# ImpactNode.net
KiCad netlist of a schematic drawn in Altium Designer
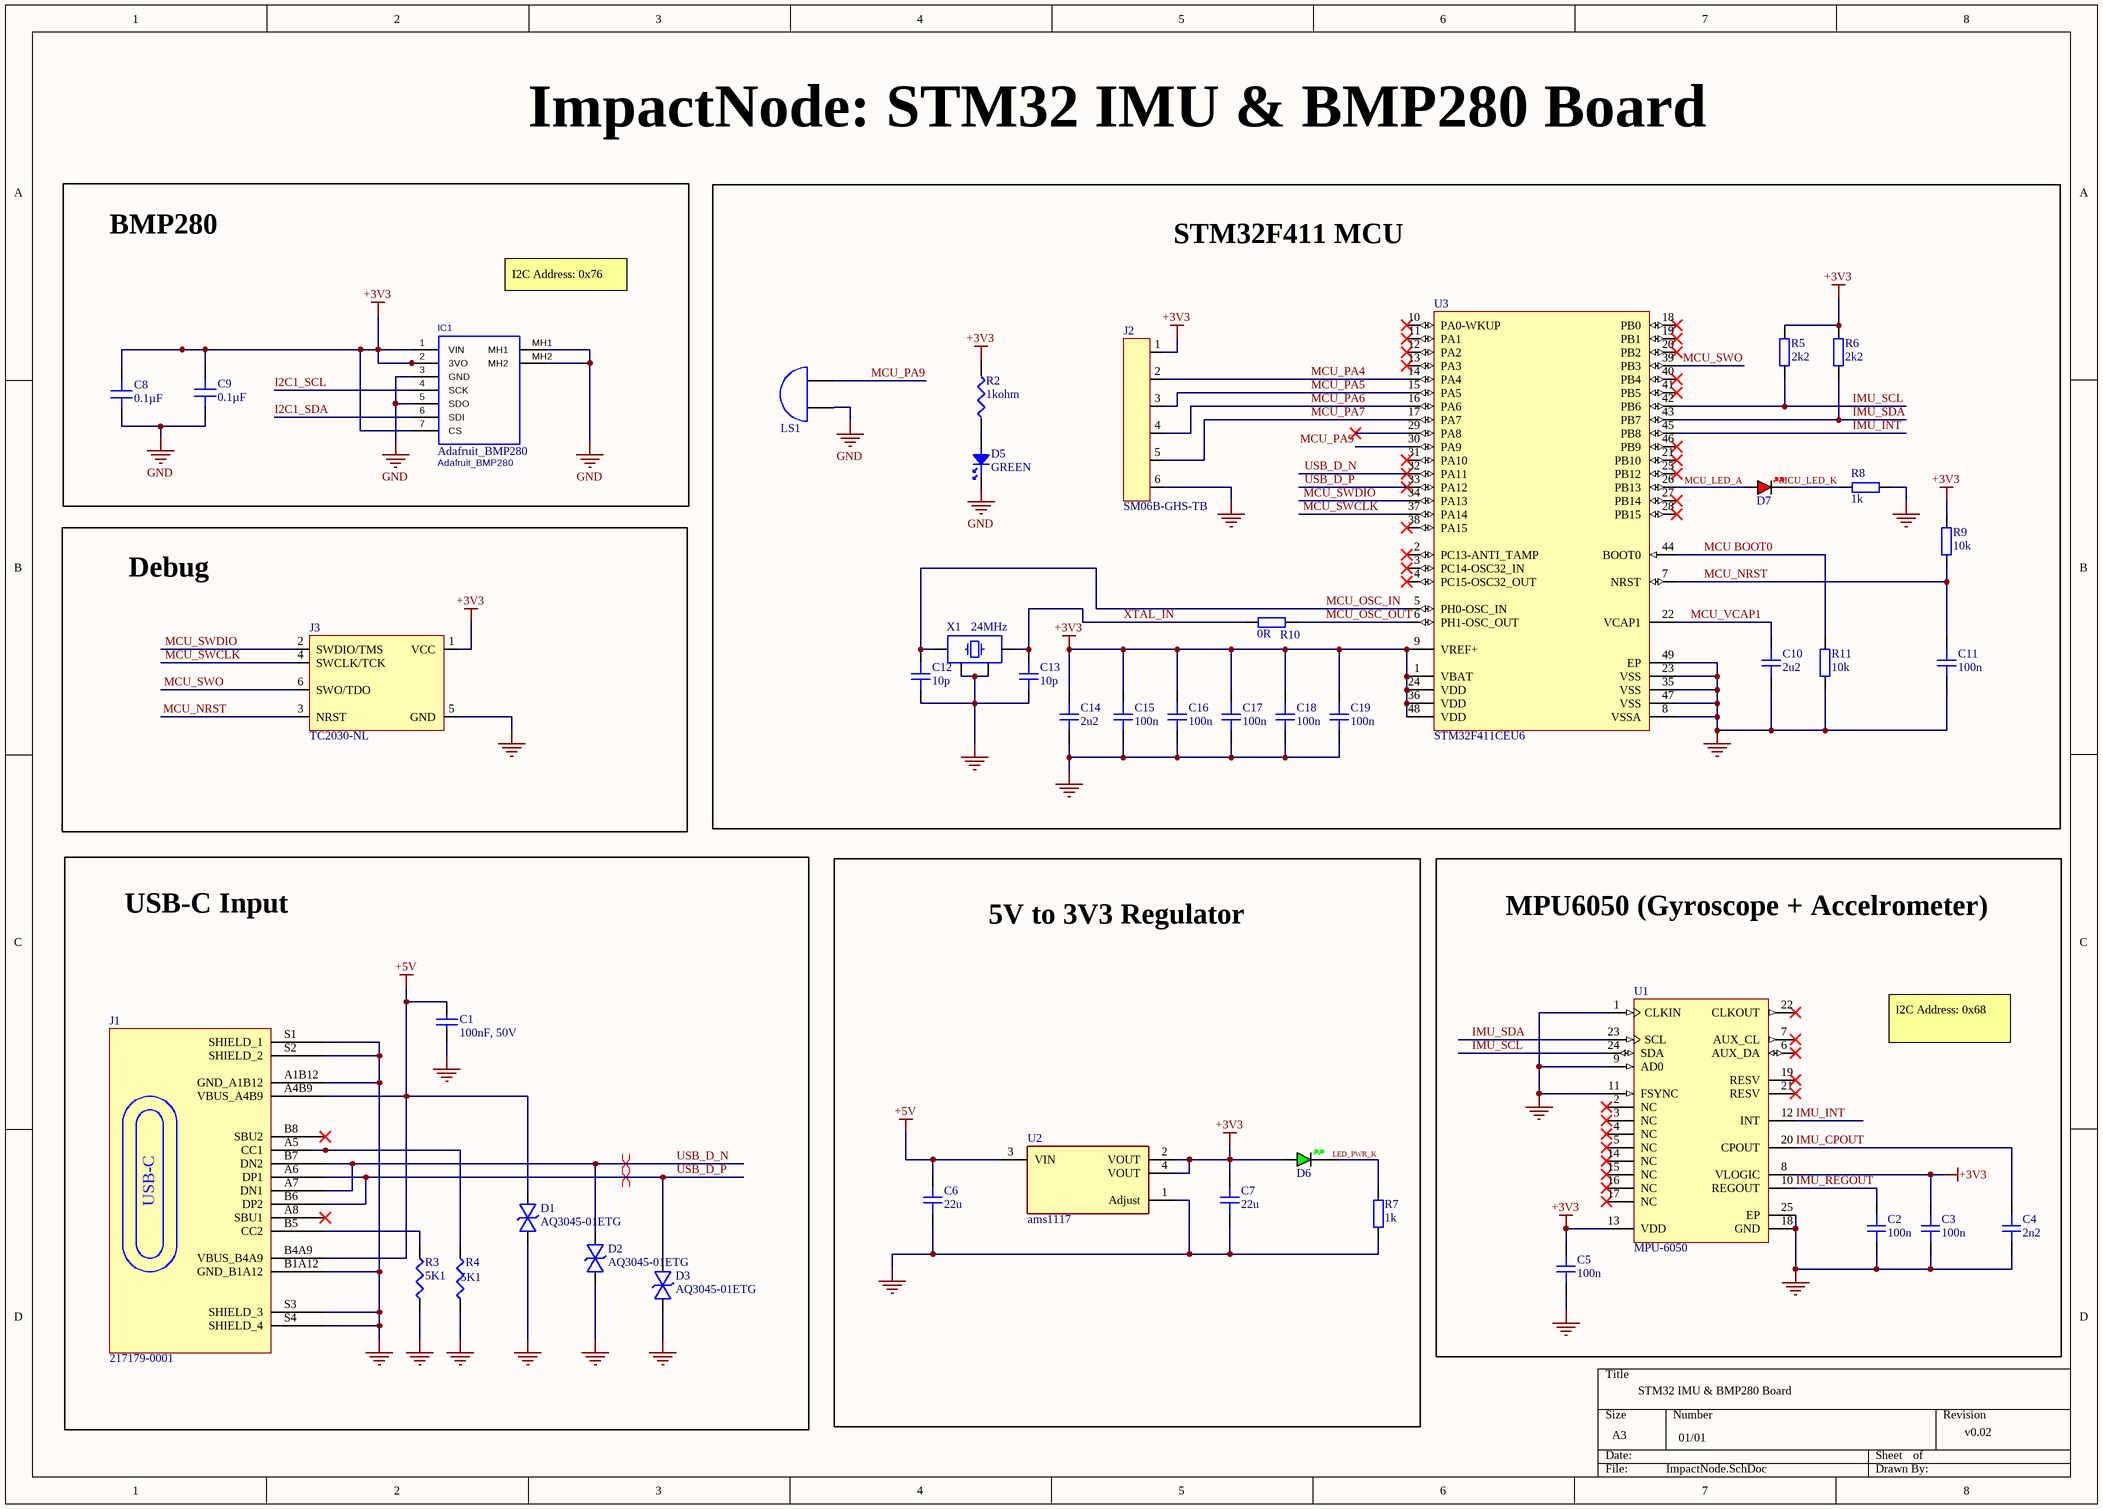
[diagram p0: ImpactNode.SchDoc]

(export (version "E")
  (design (tool "Eeschema 10.0.6"))
  (components
    (comp (ref "C1")
      (value "100nF, 50V")
      (footprint "CAPC1005X55N")
      (description "CAP CER 0.1UF 50V X7R 0402")
      (fields
        (field (name "MANUFACTURER") "Samsung Electro-Mechanics")
        (field (name "MANUFACTURER PART NUMBER") "CL05B104KB5NNNC")
      )
      (libsource (lib "SchLIb") (part "CL05B104KB5NNNC"))
    )
    (comp (ref "C2")
      (value "100n")
      (footprint "CAP_0402")
      (description "Capacitor SMD 0402 16V")
      (libsource (lib "Schematic-Lib-PhilsLab") (part "CAP_0402"))
    )
    (comp (ref "C3")
      (value "100n")
      (footprint "CAP_0402")
      (description "Capacitor SMD 0402 16V")
      (libsource (lib "Schematic-Lib-PhilsLab") (part "CAP_0402"))
    )
    (comp (ref "C4")
      (value "2n2")
      (footprint "CAP_0402")
      (description "Capacitor SMD 0402 16V")
      (libsource (lib "Schematic-Lib-PhilsLab") (part "CAP_0402"))
    )
    (comp (ref "C5")
      (value "100n")
      (footprint "CAP_0402")
      (description "Capacitor SMD 0402")
      (libsource (lib "Schematic-Lib-PhilsLab") (part "CAP_0402"))
    )
    (comp (ref "C6")
      (value "22u")
      (footprint "CAP_0805")
      (description "Capacitor SMD 0805 16V")
      (libsource (lib "Schematic-Lib-PhilsLab") (part "CAP_0805"))
    )
    (comp (ref "C7")
      (value "22u")
      (footprint "CAP_0805")
      (description "Capacitor SMD 0805 16V")
      (libsource (lib "Schematic-Lib-PhilsLab") (part "CAP_0805"))
    )
    (comp (ref "C8")
      (value "0.1µF")
      (footprint "CAP 0603_1608")
      (description "CAP CER 0.1UF 10V X7R 0603")
      (fields
        (field (name "PART NUMBER") "LD03ZC104KAB2A")
        (field (name "CAPACITANCE") "0.1µF")
        (field (name "MANUFACTURER") "AVX Corporation")
      )
      (libsource (lib "Celestial Altium Library - altium_library") (part "Capacitor"))
    )
    (comp (ref "C9")
      (value "0.1µF")
      (footprint "CAP 0603_1608")
      (description "CAP CER 0.1UF 10V X7R 0603")
      (fields
        (field (name "PART NUMBER") "LD03ZC104KAB2A")
        (field (name "CAPACITANCE") "0.1µF")
        (field (name "MANUFACTURER") "AVX Corporation")
      )
      (libsource (lib "Celestial Altium Library - altium_library") (part "Capacitor"))
    )
    (comp (ref "C10")
      (value "2u2")
      (footprint "CAP_0603")
      (description "Capacitor SMD 0603")
      (libsource (lib "Schematic-Lib-PhilsLab") (part "CAP_0603"))
    )
    (comp (ref "C11")
      (value "100n")
      (footprint "CAP_0402")
      (description "Capacitor SMD 0402")
      (libsource (lib "Schematic-Lib-PhilsLab") (part "CAP_0402"))
    )
    (comp (ref "C12")
      (value "10p")
      (footprint "CAP_0402")
      (description "Capacitor SMD 0402 16V")
      (libsource (lib "Schematic-Lib-PhilsLab") (part "CAP_0402"))
    )
    (comp (ref "C13")
      (value "10p")
      (footprint "CAP_0402")
      (description "Capacitor SMD 0402 16V")
      (libsource (lib "Schematic-Lib-PhilsLab") (part "CAP_0402"))
    )
    (comp (ref "C14")
      (value "2u2")
      (footprint "CAP_0603")
      (description "Capacitor SMD 0603")
      (libsource (lib "Schematic-Lib-PhilsLab") (part "CAP_0603"))
    )
    (comp (ref "C15")
      (value "100n")
      (footprint "CAP_0402")
      (description "Capacitor SMD 0402")
      (libsource (lib "Schematic-Lib-PhilsLab") (part "CAP_0402"))
    )
    (comp (ref "C16")
      (value "100n")
      (footprint "CAP_0402")
      (description "Capacitor SMD 0402")
      (libsource (lib "Schematic-Lib-PhilsLab") (part "CAP_0402"))
    )
    (comp (ref "C17")
      (value "100n")
      (footprint "CAP_0402")
      (description "Capacitor SMD 0402")
      (libsource (lib "Schematic-Lib-PhilsLab") (part "CAP_0402"))
    )
    (comp (ref "C18")
      (value "100n")
      (footprint "CAP_0402")
      (description "Capacitor SMD 0402")
      (libsource (lib "Schematic-Lib-PhilsLab") (part "CAP_0402"))
    )
    (comp (ref "C19")
      (value "100n")
      (footprint "CAP_0402")
      (description "Capacitor SMD 0402")
      (libsource (lib "Schematic-Lib-PhilsLab") (part "CAP_0402"))
    )
    (comp (ref "D1")
      (value "AQ3045-01ETG")
      (footprint "SOD882")
      (description "Bi 30Kv 5V 0.35Pf Automotve Tvs Sod882/ T&r Rohs Compliant: Yes ¦Littelfuse AQ3045-01ETG")
      (fields (field (name "MANUFACTURER") "Littelfuse"))
      (libsource (lib "SchLIb") (part "AQ3045-01ETG"))
    )
    (comp (ref "D2")
      (value "AQ3045-01ETG")
      (footprint "SOD882")
      (description "Bi 30Kv 5V 0.35Pf Automotve Tvs Sod882/ T&r Rohs Compliant: Yes ¦Littelfuse AQ3045-01ETG")
      (fields (field (name "MANUFACTURER") "Littelfuse"))
      (libsource (lib "SchLIb") (part "AQ3045-01ETG"))
    )
    (comp (ref "D3")
      (value "AQ3045-01ETG")
      (footprint "SOD882")
      (description "Bi 30Kv 5V 0.35Pf Automotve Tvs Sod882/ T&r Rohs Compliant: Yes ¦Littelfuse AQ3045-01ETG")
      (fields (field (name "MANUFACTURER") "Littelfuse"))
      (libsource (lib "SchLIb") (part "AQ3045-01ETG"))
    )
    (comp (ref "D5")
      (value "GREEN")
      (footprint "LED_0603")
      (description "Single Color LED, Yellow Green, 0.5mm")
      (fields
        (field (name "MANUFACTURER") "Vishay")
        (field (name "MANUFACTURER PART NUMBER") "VLMG1500-GS08")
      )
      (libsource (lib "Schlib") (part "VLMG1500-GS08"))
    )
    (comp (ref "D6")
      (value "GREEN")
      (footprint "LED_0402_GREEN")
      (description "LED 0402 GREEN SMD")
      (libsource (lib "Schematic-Lib-PhilsLab") (part "LED_0402_GREEN"))
    )
    (comp (ref "D7")
      (value "RED")
      (footprint "LED_0402_RED")
      (description "LED 0402 RED SMD")
      (libsource (lib "Schematic-Lib-PhilsLab") (part "LED_0402_RED"))
    )
    (comp (ref "IC1")
      (value "Adafruit_BMP280")
      (footprint "AdafruitBMP280")
      (description "Adafruit BMP280 Barometric Pressure + Temperature Sensor Breakout")
      (fields
        (field (name "MANUFACTURER_PART_NUMBER") "Adafruit BMP280")
        (field (name "ALTIUM_VALUE") "Adafruit_BMP280")
      )
      (libsource (lib "Adafruit_BMP280") (part "Adafruit_BMP280"))
    )
    (comp (ref "J1")
      (value "217179-0001")
      (footprint "FP-2171790001-MFG")
      (description "USB Connector, USB Type C, USB 2.0, Receptacle, 16 Ways, Surface Mount, Through Hole Mount")
      (fields (field (name "MANUFACTURER") "Molex") (field (name "LCSC PART NUMBER") "C3197684"))
      (libsource (lib "SchLIb") (part "217179-0001"))
    )
    (comp (ref "J2")
      (value "SM06B-GHS-TB")
      (footprint "HDR1X6")
      (description "Header Connector 6 Position 1.25MM Pitch SMD Horizontal JST GH")
      (fields (field (name "MANUFACTURER") "JST"))
      (libsource (lib "Schematic-Lib-PhilsLab") (part "SM06B-GHS-TB"))
    )
    (comp (ref "J3")
      (value "TC2030-NL")
      (footprint "TC2030-NL-FP")
      (description "Tag-Connect No-Solder SWD Debug Connector (No Legs) DO NOT PLACE")
      (fields
        (field (name "MANUFACTURER") "Tag-Connect")
        (field (name "MANUFACTURER PART NUMBER") "TC2030-NL-FP")
      )
      (libsource (lib "Schematic-Lib-PhilsLab") (part "TC2030-NL"))
    )
    (comp (ref "LS1")
      (value "buzzer")
      (footprint "PIN2")
      (description "Buzzer")
      (fields (field (name "PUBLISHER") "Altium Limited"))
      (libsource (lib "Miscellaneous Devices") (part "Bell"))
    )
    (comp (ref "R2")
      (value "1kohm")
      (footprint "R0402")
      (description "RES 1K OHM 1% 1/16W 0402")
      (fields
        (field (name "MANUFACTURER") "Yageo")
        (field (name "MANUFACTURER PART NUMBER") "RC0402FR-071KL")
      )
      (libsource (lib "Schlib") (part "RC0402FR-071KL"))
    )
    (comp (ref "R3")
      (value "5K1")
      (footprint "RESC1005X37N")
      (description "Res Thick Film 0402 5.1K Ohm 1% 0.063W(1/16W) ±100ppm/C Pad SMD Automotive T/R")
      (fields
        (field (name "MANUFACTURER") "Yageo Group")
        (field (name "MANUFACTURER PART NUMBER") "AC0402FR-075K1L")
      )
      (libsource (lib "SchLIb") (part "AC0402FR-075K1L"))
    )
    (comp (ref "R4")
      (value "5K1")
      (footprint "RESC1005X37N")
      (description "Res Thick Film 0402 5.1K Ohm 1% 0.063W(1/16W) ±100ppm/C Pad SMD Automotive T/R")
      (fields
        (field (name "MANUFACTURER") "Yageo Group")
        (field (name "MANUFACTURER PART NUMBER") "AC0402FR-075K1L")
      )
      (libsource (lib "SchLIb") (part "AC0402FR-075K1L"))
    )
    (comp (ref "R5")
      (value "2k2")
      (footprint "RES_0402")
      (description "Resistor SMD 0402")
      (libsource (lib "Schematic-Lib-PhilsLab") (part "RES_0402"))
    )
    (comp (ref "R6")
      (value "2k2")
      (footprint "RES_0402")
      (description "Resistor SMD 0402")
      (libsource (lib "Schematic-Lib-PhilsLab") (part "RES_0402"))
    )
    (comp (ref "R7")
      (value "1k")
      (footprint "RES_0402")
      (description "Resistor SMD 0402")
      (libsource (lib "Schematic-Lib-PhilsLab") (part "RES_0402"))
    )
    (comp (ref "R8")
      (value "1k")
      (footprint "RES_0402")
      (description "Resistor SMD 0402")
      (libsource (lib "Schematic-Lib-PhilsLab") (part "RES_0402"))
    )
    (comp (ref "R9")
      (value "10k")
      (footprint "RES_0402")
      (description "Resistor SMD 0402")
      (libsource (lib "Schematic-Lib-PhilsLab") (part "RES_0402"))
    )
    (comp (ref "R10")
      (value "0R")
      (footprint "RES_0402")
      (description "Resistor SMD 0402 0R")
      (libsource (lib "Schematic-Lib-PhilsLab") (part "RES_0402"))
    )
    (comp (ref "R11")
      (value "10k")
      (footprint "RES_0402")
      (description "Resistor SMD 0402")
      (libsource (lib "Schematic-Lib-PhilsLab") (part "RES_0402"))
    )
    (comp (ref "U1")
      (value "MPU-6050")
      (footprint "IS-QFN-24_V")
      (fields (field (name "MANUFACTURER") "InvenSense"))
      (libsource (lib "Altium Content Vault") (part "IS-MPU-6050-QFN-24"))
    )
    (comp (ref "U2")
      (value "ams1117")
      (footprint "FP-ams1117-IPC_C")
      (description "1A LOW DROPOUT VOLTAGE REGULATOR")
      (libsource (lib "Altium Content Vault") (part "59ad430b93a2c51b3e6ee7c3b069677"))
    )
    (comp (ref "U3")
      (value "STM32F411CEU6")
      (footprint "STM-UFQFPN48_L")
      (libsource (lib "Altium Content Vault") (part "MC-ARM-STM32F411-UFQFPN48"))
    )
    (comp (ref "X1")
      (value "24MHz")
      (footprint "XTAL_3225")
      (description "Crystal SMD 24MHz 10PPM 7pF 3225")
      (fields
        (field (name "MANUFACTURER") "Epson")
        (field (name "MANUFACTURER PART NUMBER") "TSX-3225 24.0000MF15X-AC")
      )
      (libsource (lib "Schematic-Lib-PhilsLab") (part "TSX-3225_24.0000MF15X-AC"))
    )
  )
  (nets
    (net (code "1") (name "+3V3") (class "Default")
      (node (ref "C14") (pin "2") (pinfunction "2_2") (pintype "passive"))
      (node (ref "C15") (pin "2") (pinfunction "2_2") (pintype "passive"))
      (node (ref "C16") (pin "2") (pinfunction "2_2") (pintype "passive"))
      (node (ref "C17") (pin "2") (pinfunction "2_2") (pintype "passive"))
      (node (ref "C18") (pin "2") (pinfunction "2_2") (pintype "passive"))
      (node (ref "C19") (pin "2") (pinfunction "2_2") (pintype "passive"))
      (node (ref "C3") (pin "2") (pinfunction "2_2") (pintype "passive"))
      (node (ref "C5") (pin "2") (pinfunction "2_2") (pintype "passive"))
      (node (ref "C7") (pin "2") (pinfunction "2_2") (pintype "passive"))
      (node (ref "C8") (pin "2") (pinfunction "2_2") (pintype "passive"))
      (node (ref "C9") (pin "2") (pinfunction "2_2") (pintype "passive"))
      (node (ref "D6") (pin "A") (pinfunction "A_A") (pintype "passive"))
      (node (ref "IC1") (pin "1") (pinfunction "VIN_1") (pintype "passive"))
      (node (ref "IC1") (pin "2") (pinfunction "3VO_2") (pintype "passive"))
      (node (ref "IC1") (pin "7") (pinfunction "CS_7") (pintype "passive"))
      (node (ref "J2") (pin "1") (pinfunction "1_1") (pintype "passive"))
      (node (ref "J3") (pin "1") (pinfunction "VCC_1") (pintype "passive"))
      (node (ref "R2") (pin "2") (pinfunction "2_2") (pintype "passive"))
      (node (ref "R5") (pin "2") (pinfunction "2_2") (pintype "passive"))
      (node (ref "R6") (pin "2") (pinfunction "2_2") (pintype "passive"))
      (node (ref "R9") (pin "2") (pinfunction "2_2") (pintype "passive"))
      (node (ref "U1") (pin "13") (pinfunction "VDD_13") (pintype "power_in"))
      (node (ref "U1") (pin "8") (pinfunction "VLOGIC_8") (pintype "power_in"))
      (node (ref "U2") (pin "2") (pinfunction "VOUT_2") (pintype "passive"))
      (node (ref "U2") (pin "4") (pinfunction "VOUT_4") (pintype "passive"))
      (node (ref "U3") (pin "1") (pinfunction "VBAT_1") (pintype "power_in"))
      (node (ref "U3") (pin "24") (pinfunction "VDD_24") (pintype "power_in"))
      (node (ref "U3") (pin "36") (pinfunction "VDD_36") (pintype "power_in"))
      (node (ref "U3") (pin "48") (pinfunction "VDD_48") (pintype "power_in"))
      (node (ref "U3") (pin "9") (pinfunction "VREF+_9") (pintype "power_in"))
    )
    (net (code "2") (name "+5V") (class "Default")
      (node (ref "C1") (pin "2") (pinfunction "2_2") (pintype "passive"))
      (node (ref "C6") (pin "2") (pinfunction "2_2") (pintype "passive"))
      (node (ref "D1") (pin "2") (pinfunction "2_2") (pintype "passive"))
      (node (ref "J1") (pin "A4B9") (pinfunction "VBUS_A4B9_A4B9") (pintype "passive"))
      (node (ref "J1") (pin "B4A9") (pinfunction "VBUS_B4A9_B4A9") (pintype "passive"))
      (node (ref "U2") (pin "3") (pinfunction "VIN_3") (pintype "power_in"))
    )
    (net (code "3") (name "/I2C1_SCL") (class "Default")
      (node (ref "IC1") (pin "4") (pinfunction "SCK_4") (pintype "passive"))
    )
    (net (code "4") (name "/I2C1_SDA") (class "Default")
      (node (ref "IC1") (pin "6") (pinfunction "SDI_6") (pintype "passive"))
    )
    (net (code "5") (name "/IMU_CPOUT") (class "Default")
      (node (ref "C4") (pin "2") (pinfunction "2_2") (pintype "passive"))
      (node (ref "U1") (pin "20") (pinfunction "CPOUT_20") (pintype "passive"))
    )
    (net (code "6") (name "/IMU_INT") (class "Default")
      (node (ref "U1") (pin "12") (pinfunction "INT_12") (pintype "open_collector"))
      (node (ref "U3") (pin "45") (pinfunction "PB8_45") (pintype "bidirectional"))
    )
    (net (code "7") (name "/IMU_REGOUT") (class "Default")
      (node (ref "C2") (pin "2") (pinfunction "2_2") (pintype "passive"))
      (node (ref "U1") (pin "10") (pinfunction "REGOUT_10") (pintype "passive"))
    )
    (net (code "8") (name "/IMU_SCL") (class "Default")
      (node (ref "R5") (pin "1") (pinfunction "1_1") (pintype "passive"))
      (node (ref "U1") (pin "24") (pinfunction "SDA_24") (pintype "bidirectional"))
      (node (ref "U3") (pin "42") (pinfunction "PB6_42") (pintype "bidirectional"))
    )
    (net (code "9") (name "/IMU_SDA") (class "Default")
      (node (ref "R6") (pin "1") (pinfunction "1_1") (pintype "passive"))
      (node (ref "U1") (pin "23") (pinfunction "SCL_23") (pintype "input"))
      (node (ref "U3") (pin "43") (pinfunction "PB7_43") (pintype "bidirectional"))
    )
    (net (code "10") (name "/LED_PWR_K") (class "Default")
      (node (ref "D6") (pin "K") (pinfunction "K_K") (pintype "passive"))
      (node (ref "R7") (pin "2") (pinfunction "2_2") (pintype "passive"))
    )
    (net (code "11") (name "/MCU BOOT0") (class "Default")
      (node (ref "R11") (pin "2") (pinfunction "2_2") (pintype "passive"))
      (node (ref "U3") (pin "44") (pinfunction "BOOT0_44") (pintype "input"))
    )
    (net (code "12") (name "/MCU_LED_A") (class "Default")
      (node (ref "D7") (pin "A") (pinfunction "A_A") (pintype "passive"))
      (node (ref "U3") (pin "26") (pinfunction "PB13_26") (pintype "bidirectional"))
    )
    (net (code "13") (name "/MCU_LED_K") (class "Default")
      (node (ref "D7") (pin "K") (pinfunction "K_K") (pintype "passive"))
      (node (ref "R8") (pin "2") (pinfunction "2_2") (pintype "passive"))
    )
    (net (code "14") (name "/MCU_NRST") (class "Default")
      (node (ref "C11") (pin "2") (pinfunction "2_2") (pintype "passive"))
      (node (ref "J3") (pin "3") (pinfunction "NRST_3") (pintype "passive"))
      (node (ref "R9") (pin "1") (pinfunction "1_1") (pintype "passive"))
      (node (ref "U3") (pin "7") (pinfunction "NRST_7") (pintype "bidirectional"))
    )
    (net (code "15") (name "/MCU_OSC_IN") (class "Default")
      (node (ref "C12") (pin "2") (pinfunction "2_2") (pintype "passive"))
      (node (ref "U3") (pin "5") (pinfunction "PH0-OSC_IN_5") (pintype "bidirectional"))
      (node (ref "X1") (pin "1") (pinfunction "1_1") (pintype "passive"))
    )
    (net (code "16") (name "/MCU_OSC_OUT") (class "Default")
      (node (ref "R10") (pin "2") (pinfunction "2_2") (pintype "passive"))
      (node (ref "U3") (pin "6") (pinfunction "PH1-OSC_OUT_6") (pintype "bidirectional"))
    )
    (net (code "17") (name "/MCU_PA4") (class "Default")
      (node (ref "J2") (pin "2") (pinfunction "2_2") (pintype "passive"))
      (node (ref "U3") (pin "14") (pinfunction "PA4_14") (pintype "bidirectional"))
    )
    (net (code "18") (name "/MCU_PA5") (class "Default")
      (node (ref "J2") (pin "3") (pinfunction "3_3") (pintype "passive"))
      (node (ref "U3") (pin "15") (pinfunction "PA5_15") (pintype "bidirectional"))
    )
    (net (code "19") (name "/MCU_PA6") (class "Default")
      (node (ref "J2") (pin "4") (pinfunction "4_4") (pintype "passive"))
      (node (ref "U3") (pin "16") (pinfunction "PA6_16") (pintype "bidirectional"))
    )
    (net (code "20") (name "/MCU_PA7") (class "Default")
      (node (ref "J2") (pin "5") (pinfunction "5_5") (pintype "passive"))
      (node (ref "U3") (pin "17") (pinfunction "PA7_17") (pintype "bidirectional"))
    )
    (net (code "21") (name "/MCU_PA9") (class "Default")
      (node (ref "LS1") (pin "2") (pinfunction "B_2") (pintype "passive"))
      (node (ref "U3") (pin "30") (pinfunction "PA9_30") (pintype "bidirectional"))
    )
    (net (code "22") (name "/MCU_SWCLK") (class "Default")
      (node (ref "J3") (pin "4") (pinfunction "SWCLK/TCK_4") (pintype "passive"))
      (node (ref "U3") (pin "37") (pinfunction "PA14_37") (pintype "bidirectional"))
    )
    (net (code "23") (name "/MCU_SWDIO") (class "Default")
      (node (ref "J3") (pin "2") (pinfunction "SWDIO/TMS_2") (pintype "passive"))
      (node (ref "U3") (pin "34") (pinfunction "PA13_34") (pintype "bidirectional"))
    )
    (net (code "24") (name "/MCU_SWO") (class "Default")
      (node (ref "J3") (pin "6") (pinfunction "SWO/TDO_6") (pintype "passive"))
      (node (ref "U3") (pin "39") (pinfunction "PB3_39") (pintype "bidirectional"))
    )
    (net (code "25") (name "/MCU_VCAP1") (class "Default")
      (node (ref "C10") (pin "2") (pinfunction "2_2") (pintype "passive"))
      (node (ref "U3") (pin "22") (pinfunction "VCAP1_22") (pintype "passive"))
    )
    (net (code "26") (name "/USB_D_N") (class "Default")
      (node (ref "D2") (pin "2") (pinfunction "2_2") (pintype "passive"))
      (node (ref "J1") (pin "A7") (pinfunction "DN1_A7") (pintype "passive"))
      (node (ref "J1") (pin "B7") (pinfunction "DN2_B7") (pintype "passive"))
      (node (ref "U3") (pin "32") (pinfunction "PA11_32") (pintype "bidirectional"))
    )
    (net (code "27") (name "/USB_D_P") (class "Default")
      (node (ref "D3") (pin "2") (pinfunction "2_2") (pintype "passive"))
      (node (ref "J1") (pin "A6") (pinfunction "DP1_A6") (pintype "passive"))
      (node (ref "J1") (pin "B6") (pinfunction "DP2_B6") (pintype "passive"))
      (node (ref "U3") (pin "33") (pinfunction "PA12_33") (pintype "bidirectional"))
    )
    (net (code "28") (name "/XTAL_IN") (class "Default")
      (node (ref "C13") (pin "2") (pinfunction "2_2") (pintype "passive"))
      (node (ref "R10") (pin "1") (pinfunction "1_1") (pintype "passive"))
      (node (ref "X1") (pin "3") (pinfunction "3_3") (pintype "passive"))
    )
    (net (code "29") (name "GND") (class "Default")
      (node (ref "C1") (pin "1") (pinfunction "1_1") (pintype "passive"))
      (node (ref "C10") (pin "1") (pinfunction "1_1") (pintype "passive"))
      (node (ref "C11") (pin "1") (pinfunction "1_1") (pintype "passive"))
      (node (ref "C12") (pin "1") (pinfunction "1_1") (pintype "passive"))
      (node (ref "C13") (pin "1") (pinfunction "1_1") (pintype "passive"))
      (node (ref "C14") (pin "1") (pinfunction "1_1") (pintype "passive"))
      (node (ref "C15") (pin "1") (pinfunction "1_1") (pintype "passive"))
      (node (ref "C16") (pin "1") (pinfunction "1_1") (pintype "passive"))
      (node (ref "C17") (pin "1") (pinfunction "1_1") (pintype "passive"))
      (node (ref "C18") (pin "1") (pinfunction "1_1") (pintype "passive"))
      (node (ref "C19") (pin "1") (pinfunction "1_1") (pintype "passive"))
      (node (ref "C2") (pin "1") (pinfunction "1_1") (pintype "passive"))
      (node (ref "C3") (pin "1") (pinfunction "1_1") (pintype "passive"))
      (node (ref "C4") (pin "1") (pinfunction "1_1") (pintype "passive"))
      (node (ref "C5") (pin "1") (pinfunction "1_1") (pintype "passive"))
      (node (ref "C6") (pin "1") (pinfunction "1_1") (pintype "passive"))
      (node (ref "C7") (pin "1") (pinfunction "1_1") (pintype "passive"))
      (node (ref "C8") (pin "1") (pinfunction "1_1") (pintype "passive"))
      (node (ref "C9") (pin "1") (pinfunction "1_1") (pintype "passive"))
      (node (ref "D1") (pin "1") (pinfunction "1_1") (pintype "passive"))
      (node (ref "D2") (pin "1") (pinfunction "1_1") (pintype "passive"))
      (node (ref "D3") (pin "1") (pinfunction "1_1") (pintype "passive"))
      (node (ref "D5") (pin "1") (pinfunction "1_1") (pintype "passive"))
      (node (ref "IC1") (pin "3") (pinfunction "GND_3") (pintype "passive"))
      (node (ref "IC1") (pin "5") (pinfunction "SDO_5") (pintype "passive"))
      (node (ref "IC1") (pin "MH1") (pinfunction "MH1_MH1") (pintype "passive"))
      (node (ref "IC1") (pin "MH2") (pinfunction "MH2_MH2") (pintype "passive"))
      (node (ref "J1") (pin "A1B12") (pinfunction "GND_A1B12_A1B12") (pintype "passive"))
      (node (ref "J1") (pin "B1A12") (pinfunction "GND_B1A12_B1A12") (pintype "passive"))
      (node (ref "J1") (pin "S1") (pinfunction "SHIELD_1_S1") (pintype "passive"))
      (node (ref "J1") (pin "S2") (pinfunction "SHIELD_2_S2") (pintype "passive"))
      (node (ref "J1") (pin "S3") (pinfunction "SHIELD_3_S3") (pintype "passive"))
      (node (ref "J1") (pin "S4") (pinfunction "SHIELD_4_S4") (pintype "passive"))
      (node (ref "J2") (pin "6") (pinfunction "6_6") (pintype "passive"))
      (node (ref "J3") (pin "5") (pinfunction "GND_5") (pintype "passive"))
      (node (ref "LS1") (pin "1") (pinfunction "A_1") (pintype "passive"))
      (node (ref "R11") (pin "1") (pinfunction "1_1") (pintype "passive"))
      (node (ref "R3") (pin "1") (pinfunction "1_1") (pintype "passive"))
      (node (ref "R4") (pin "1") (pinfunction "1_1") (pintype "passive"))
      (node (ref "R7") (pin "1") (pinfunction "1_1") (pintype "passive"))
      (node (ref "R8") (pin "1") (pinfunction "1_1") (pintype "passive"))
      (node (ref "U1") (pin "1") (pinfunction "CLKIN_1") (pintype "input"))
      (node (ref "U1") (pin "11") (pinfunction "FSYNC_11") (pintype "input"))
      (node (ref "U1") (pin "18") (pinfunction "GND_18") (pintype "power_in"))
      (node (ref "U1") (pin "25") (pinfunction "EP_25") (pintype "power_in"))
      (node (ref "U1") (pin "9") (pinfunction "AD0_9") (pintype "input"))
      (node (ref "U2") (pin "1") (pinfunction "Adjust_1") (pintype "passive"))
      (node (ref "U3") (pin "23") (pinfunction "VSS_23") (pintype "power_in"))
      (node (ref "U3") (pin "35") (pinfunction "VSS_35") (pintype "power_in"))
      (node (ref "U3") (pin "47") (pinfunction "VSS_47") (pintype "power_in"))
      (node (ref "U3") (pin "49") (pinfunction "EP_49") (pintype "power_in"))
      (node (ref "U3") (pin "8") (pinfunction "VSSA_8") (pintype "power_in"))
      (node (ref "X1") (pin "2") (pinfunction "2_2") (pintype "passive"))
      (node (ref "X1") (pin "4") (pinfunction "4_4") (pintype "passive"))
    )
    (net (code "30") (name "Net-(D5-Pad2)") (class "Default")
      (node (ref "D5") (pin "2") (pinfunction "2_2") (pintype "passive"))
      (node (ref "R2") (pin "1") (pinfunction "1_1") (pintype "passive"))
    )
    (net (code "31") (name "Net-(J1-CC1)") (class "Default")
      (node (ref "J1") (pin "A5") (pinfunction "CC1_A5") (pintype "passive"))
      (node (ref "R4") (pin "2") (pinfunction "2_2") (pintype "passive"))
    )
    (net (code "32") (name "Net-(J1-CC2)") (class "Default")
      (node (ref "J1") (pin "B5") (pinfunction "CC2_B5") (pintype "passive"))
      (node (ref "R3") (pin "2") (pinfunction "2_2") (pintype "passive"))
    )
    (net (code "33") (name "unconnected-(J1-SBU1-PadA8)") (class "Default")
      (node (ref "J1") (pin "A8") (pinfunction "SBU1_A8") (pintype "passive+no_connect"))
    )
    (net (code "34") (name "unconnected-(J1-SBU2-PadB8)") (class "Default")
      (node (ref "J1") (pin "B8") (pinfunction "SBU2_B8") (pintype "passive+no_connect"))
    )
    (net (code "35") (name "unconnected-(U1-AUX_CL-Pad7)") (class "Default")
      (node (ref "U1") (pin "7") (pinfunction "AUX_CL_7") (pintype "output+no_connect"))
    )
    (net (code "36") (name "unconnected-(U1-AUX_DA-Pad6)") (class "Default")
      (node (ref "U1") (pin "6") (pinfunction "AUX_DA_6") (pintype "bidirectional+no_connect"))
    )
    (net (code "37") (name "unconnected-(U1-CLKOUT-Pad22)") (class "Default")
      (node (ref "U1") (pin "22") (pinfunction "CLKOUT_22") (pintype "output+no_connect"))
    )
    (net (code "38") (name "unconnected-(U1-NC-Pad2)") (class "Default")
      (node (ref "U1") (pin "2") (pinfunction "NC_2") (pintype "passive+no_connect"))
    )
    (net (code "39") (name "unconnected-(U1-NC-Pad3)") (class "Default")
      (node (ref "U1") (pin "3") (pinfunction "NC_3") (pintype "passive+no_connect"))
    )
    (net (code "40") (name "unconnected-(U1-NC-Pad4)") (class "Default")
      (node (ref "U1") (pin "4") (pinfunction "NC_4") (pintype "passive+no_connect"))
    )
    (net (code "41") (name "unconnected-(U1-NC-Pad5)") (class "Default")
      (node (ref "U1") (pin "5") (pinfunction "NC_5") (pintype "passive+no_connect"))
    )
    (net (code "42") (name "unconnected-(U1-NC-Pad14)") (class "Default")
      (node (ref "U1") (pin "14") (pinfunction "NC_14") (pintype "passive+no_connect"))
    )
    (net (code "43") (name "unconnected-(U1-NC-Pad15)") (class "Default")
      (node (ref "U1") (pin "15") (pinfunction "NC_15") (pintype "passive+no_connect"))
    )
    (net (code "44") (name "unconnected-(U1-NC-Pad16)") (class "Default")
      (node (ref "U1") (pin "16") (pinfunction "NC_16") (pintype "passive+no_connect"))
    )
    (net (code "45") (name "unconnected-(U1-NC-Pad17)") (class "Default")
      (node (ref "U1") (pin "17") (pinfunction "NC_17") (pintype "passive+no_connect"))
    )
    (net (code "46") (name "unconnected-(U1-RESV-Pad19)") (class "Default")
      (node (ref "U1") (pin "19") (pinfunction "RESV_19") (pintype "passive+no_connect"))
    )
    (net (code "47") (name "unconnected-(U1-RESV-Pad21)") (class "Default")
      (node (ref "U1") (pin "21") (pinfunction "RESV_21") (pintype "passive+no_connect"))
    )
    (net (code "48") (name "unconnected-(U3-PA0-WKUP-Pad10)") (class "Default")
      (node (ref "U3") (pin "10") (pinfunction "PA0-WKUP_10") (pintype "bidirectional+no_connect"))
    )
    (net (code "49") (name "unconnected-(U3-PA1-Pad11)") (class "Default")
      (node (ref "U3") (pin "11") (pinfunction "PA1_11") (pintype "bidirectional+no_connect"))
    )
    (net (code "50") (name "unconnected-(U3-PA2-Pad12)") (class "Default")
      (node (ref "U3") (pin "12") (pinfunction "PA2_12") (pintype "bidirectional+no_connect"))
    )
    (net (code "51") (name "unconnected-(U3-PA3-Pad13)") (class "Default")
      (node (ref "U3") (pin "13") (pinfunction "PA3_13") (pintype "bidirectional+no_connect"))
    )
    (net (code "52") (name "unconnected-(U3-PA8-Pad29)") (class "Default")
      (node (ref "U3") (pin "29") (pinfunction "PA8_29") (pintype "bidirectional+no_connect"))
    )
    (net (code "53") (name "unconnected-(U3-PA10-Pad31)") (class "Default")
      (node (ref "U3") (pin "31") (pinfunction "PA10_31") (pintype "bidirectional+no_connect"))
    )
    (net (code "54") (name "unconnected-(U3-PA15-Pad38)") (class "Default")
      (node (ref "U3") (pin "38") (pinfunction "PA15_38") (pintype "bidirectional+no_connect"))
    )
    (net (code "55") (name "unconnected-(U3-PB0-Pad18)") (class "Default")
      (node (ref "U3") (pin "18") (pinfunction "PB0_18") (pintype "bidirectional+no_connect"))
    )
    (net (code "56") (name "unconnected-(U3-PB1-Pad19)") (class "Default")
      (node (ref "U3") (pin "19") (pinfunction "PB1_19") (pintype "bidirectional+no_connect"))
    )
    (net (code "57") (name "unconnected-(U3-PB2-Pad20)") (class "Default")
      (node (ref "U3") (pin "20") (pinfunction "PB2_20") (pintype "bidirectional+no_connect"))
    )
    (net (code "58") (name "unconnected-(U3-PB4-Pad40)") (class "Default")
      (node (ref "U3") (pin "40") (pinfunction "PB4_40") (pintype "bidirectional+no_connect"))
    )
    (net (code "59") (name "unconnected-(U3-PB5-Pad41)") (class "Default")
      (node (ref "U3") (pin "41") (pinfunction "PB5_41") (pintype "bidirectional+no_connect"))
    )
    (net (code "60") (name "unconnected-(U3-PB9-Pad46)") (class "Default")
      (node (ref "U3") (pin "46") (pinfunction "PB9_46") (pintype "bidirectional+no_connect"))
    )
    (net (code "61") (name "unconnected-(U3-PB10-Pad21)") (class "Default")
      (node (ref "U3") (pin "21") (pinfunction "PB10_21") (pintype "bidirectional+no_connect"))
    )
    (net (code "62") (name "unconnected-(U3-PB12-Pad25)") (class "Default")
      (node (ref "U3") (pin "25") (pinfunction "PB12_25") (pintype "bidirectional+no_connect"))
    )
    (net (code "63") (name "unconnected-(U3-PB14-Pad27)") (class "Default")
      (node (ref "U3") (pin "27") (pinfunction "PB14_27") (pintype "bidirectional+no_connect"))
    )
    (net (code "64") (name "unconnected-(U3-PB15-Pad28)") (class "Default")
      (node (ref "U3") (pin "28") (pinfunction "PB15_28") (pintype "bidirectional+no_connect"))
    )
    (net (code "65") (name "unconnected-(U3-PC13-ANTI_TAMP-Pad2)") (class "Default")
      (node (ref "U3") (pin "2") (pinfunction "PC13-ANTI_TAMP_2") (pintype "bidirectional+no_connect"))
    )
    (net (code "66") (name "unconnected-(U3-PC14-OSC32_IN-Pad3)") (class "Default")
      (node (ref "U3") (pin "3") (pinfunction "PC14-OSC32_IN_3") (pintype "bidirectional+no_connect"))
    )
    (net (code "67") (name "unconnected-(U3-PC15-OSC32_OUT-Pad4)") (class "Default")
      (node (ref "U3") (pin "4") (pinfunction "PC15-OSC32_OUT_4") (pintype "bidirectional+no_connect"))
    )
  )
)
